# frm-voltrod_AFE.net
KiCad netlist of a schematic drawn in Altium Designer
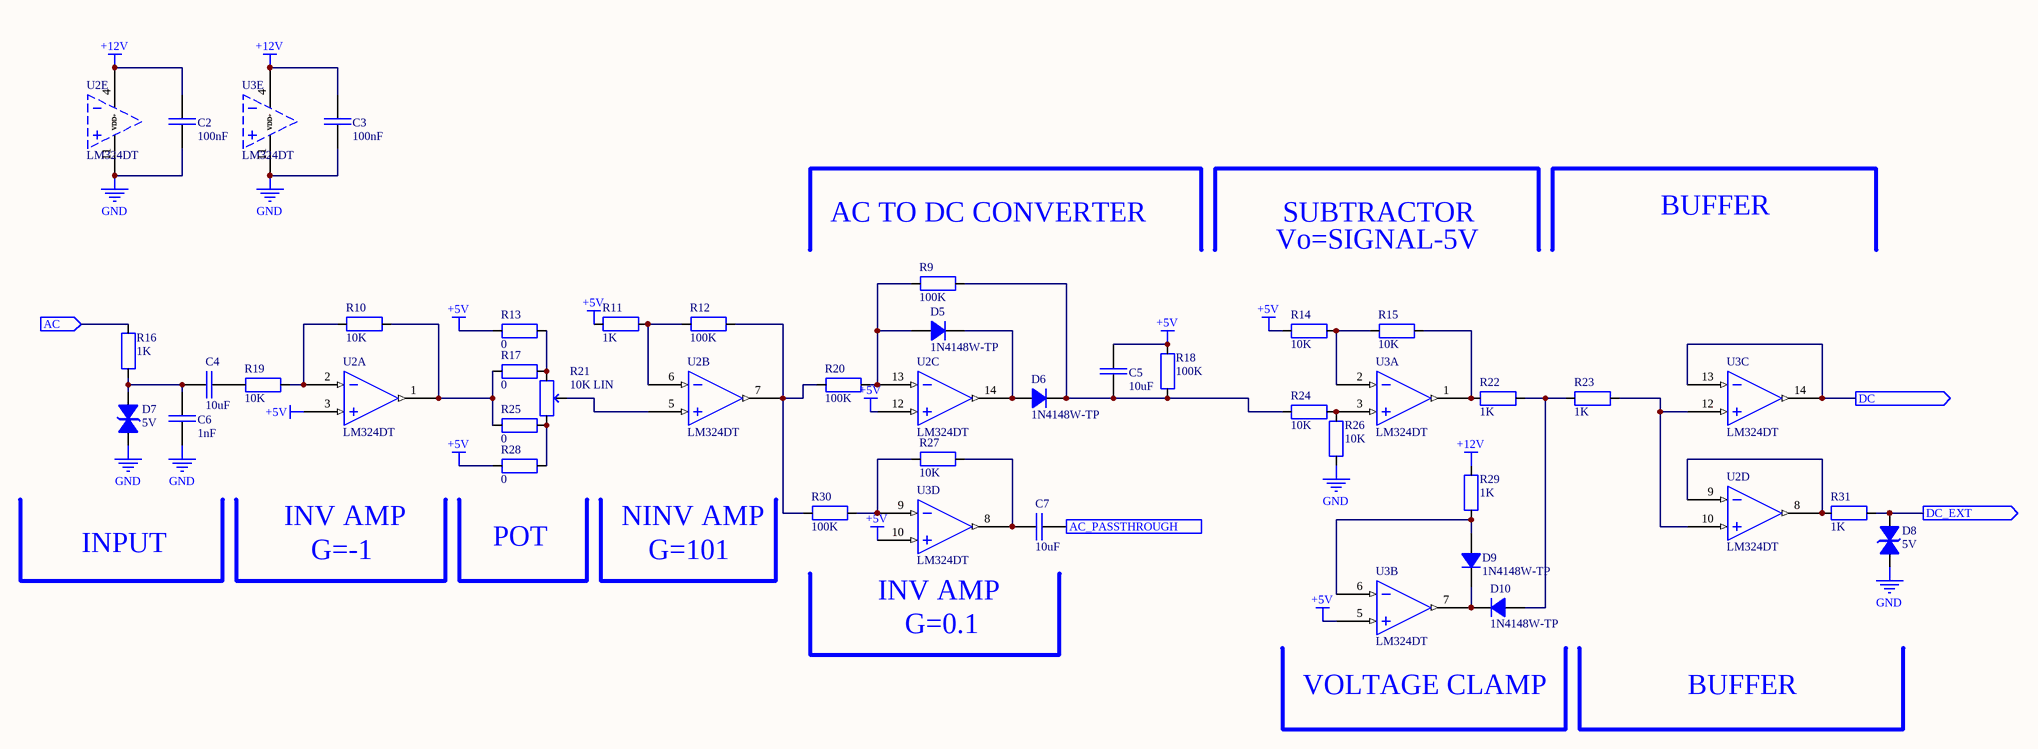
[diagram p0: frm-voltrod_AFE.SchDoc]

(export (version "E")
  (design (tool "Eeschema 10.0.6"))
  (components
    (comp (ref "C2")
      (value "100nF")
      (footprint "CAP 0603_1608")
      (description "CAP SMD MLCC 100nF 25V 0603 X7R")
      (fields (field (name "PART NUMBER") "02841f84-ac15-41b5-9e17-915f8f067828"))
      (libsource (lib "frmdblib") (part "GENERIC_C"))
    )
    (comp (ref "C3")
      (value "100nF")
      (footprint "CAP 0603_1608")
      (description "CAP SMD MLCC 100nF 25V 0603 X7R")
      (fields (field (name "PART NUMBER") "02841f84-ac15-41b5-9e17-915f8f067828"))
      (libsource (lib "frmdblib") (part "GENERIC_C"))
    )
    (comp (ref "C4")
      (value "10uF")
      (footprint "CAP 0805_2012")
      (description "CAP SMD MLCC 10uF 25V 0805 X5R")
      (fields (field (name "PART NUMBER") "1ffbe5a9-0884-4740-bdad-20a6a98400e6"))
      (libsource (lib "frmdblib") (part "GENERIC_C"))
    )
    (comp (ref "C5")
      (value "10uF")
      (footprint "CAP 0805_2012")
      (description "CAP SMD MLCC 10uF 25V 0805 X5R")
      (fields (field (name "PART NUMBER") "1ffbe5a9-0884-4740-bdad-20a6a98400e6"))
      (libsource (lib "frmdblib") (part "GENERIC_C"))
    )
    (comp (ref "C6")
      (value "1nF")
      (footprint "CAP 0603_1608")
      (description "CAP SMD MLCC 1nF 50V 0603 X7R")
      (fields (field (name "PART NUMBER") "0eca2548-3630-4fea-a3d5-94248c1cae74"))
      (libsource (lib "frmdblib") (part "GENERIC_C"))
    )
    (comp (ref "C7")
      (value "10uF")
      (footprint "CAP 0805_2012")
      (description "CAP SMD MLCC 10uF 25V 0805 X5R")
      (fields (field (name "PART NUMBER") "1ffbe5a9-0884-4740-bdad-20a6a98400e6"))
      (libsource (lib "frmdblib") (part "GENERIC_C"))
    )
    (comp (ref "D5")
      (value "1N4148W-TP")
      (footprint "SOD-123")
      (description "DIODE SMD 100V 150mA 1.5Vf SOD-123 4148")
      (fields (field (name "PART NUMBER") "5e920700-75df-48e3-84dd-8f9f777caed8"))
      (libsource (lib "frmdblib") (part "GENERIC_D"))
    )
    (comp (ref "D6")
      (value "1N4148W-TP")
      (footprint "SOD-123")
      (description "DIODE SMD 100V 150mA 1.5Vf SOD-123 4148")
      (fields (field (name "PART NUMBER") "5e920700-75df-48e3-84dd-8f9f777caed8"))
      (libsource (lib "frmdblib") (part "GENERIC_D"))
    )
    (comp (ref "D7")
      (value "5V")
      (footprint "SOD523F")
      (description "DIODE SMD TVS 5V BIDIRECTIONAL SOD-523")
      (fields (field (name "PART NUMBER") "daa58212-38e2-4326-a156-8e48058c46f1"))
      (libsource (lib "frmdblib") (part "GENERIC_D_TVS_BI"))
    )
    (comp (ref "D8")
      (value "5V")
      (footprint "SOD523F")
      (description "DIODE SMD TVS 5V BIDIRECTIONAL SOD-523")
      (fields (field (name "PART NUMBER") "daa58212-38e2-4326-a156-8e48058c46f1"))
      (libsource (lib "frmdblib") (part "GENERIC_D_TVS_BI"))
    )
    (comp (ref "D9")
      (value "1N4148W-TP")
      (footprint "SOD-123")
      (description "DIODE SMD 100V 150mA 1.5Vf SOD-123 4148")
      (fields (field (name "PART NUMBER") "5e920700-75df-48e3-84dd-8f9f777caed8"))
      (libsource (lib "frmdblib") (part "GENERIC_D"))
    )
    (comp (ref "D10")
      (value "1N4148W-TP")
      (footprint "SOD-123")
      (description "DIODE SMD 100V 150mA 1.5Vf SOD-123 4148")
      (fields (field (name "PART NUMBER") "5e920700-75df-48e3-84dd-8f9f777caed8"))
      (libsource (lib "frmdblib") (part "GENERIC_D"))
    )
    (comp (ref "R9")
      (value "100K")
      (footprint "RES 0603_1608")
      (description "RES SMD 100K OHM 1% 1/10W 0603")
      (fields (field (name "PART NUMBER") "76af10b3-9d85-4b5c-a2d6-26cc74f432f7"))
      (libsource (lib "frmdblib") (part "GENERIC_R"))
    )
    (comp (ref "R10")
      (value "10K")
      (footprint "RES 0603_1608")
      (description "RES SMD 10K OHM 1% 1/10W 0603")
      (fields (field (name "PART NUMBER") "93242766-ba1d-462d-b58f-ce1dfc4129c8"))
      (libsource (lib "frmdblib") (part "GENERIC_R"))
    )
    (comp (ref "R11")
      (value "1K")
      (footprint "RES 0603_1608")
      (description "RES SMD 1K OHM 1% 1/10W 0603")
      (fields (field (name "PART NUMBER") "a678220f-9e9d-4863-a833-9993504f723c"))
      (libsource (lib "frmdblib") (part "GENERIC_R"))
    )
    (comp (ref "R12")
      (value "100K")
      (footprint "RES 0603_1608")
      (description "RES SMD 100K OHM 1% 1/10W 0603")
      (fields (field (name "PART NUMBER") "76af10b3-9d85-4b5c-a2d6-26cc74f432f7"))
      (libsource (lib "frmdblib") (part "GENERIC_R"))
    )
    (comp (ref "R13")
      (value "0")
      (footprint "RES 0603_1608")
      (description "RES SMD 0 OHM 5% 1/10W 0603")
      (fields (field (name "PART NUMBER") "6ae227f9-847f-4766-8522-e11a83531204"))
      (libsource (lib "frmdblib") (part "GENERIC_R"))
    )
    (comp (ref "R14")
      (value "10K")
      (footprint "RES 0603_1608")
      (description "RES SMD 10K OHM 1% 1/10W 0603")
      (fields (field (name "PART NUMBER") "93242766-ba1d-462d-b58f-ce1dfc4129c8"))
      (libsource (lib "frmdblib") (part "GENERIC_R"))
    )
    (comp (ref "R15")
      (value "10K")
      (footprint "RES 0603_1608")
      (description "RES SMD 10K OHM 1% 1/10W 0603")
      (fields (field (name "PART NUMBER") "93242766-ba1d-462d-b58f-ce1dfc4129c8"))
      (libsource (lib "frmdblib") (part "GENERIC_R"))
    )
    (comp (ref "R16")
      (value "1K")
      (footprint "RES 0603_1608")
      (description "RES SMD 1K OHM 1% 1/10W 0603")
      (fields (field (name "PART NUMBER") "a678220f-9e9d-4863-a833-9993504f723c"))
      (libsource (lib "frmdblib") (part "GENERIC_R"))
    )
    (comp (ref "R17")
      (value "0")
      (footprint "RES 0603_1608")
      (description "RES SMD 0 OHM 5% 1/10W 0603")
      (fields (field (name "PART NUMBER") "6ae227f9-847f-4766-8522-e11a83531204"))
      (libsource (lib "frmdblib") (part "GENERIC_R"))
    )
    (comp (ref "R18")
      (value "100K")
      (footprint "RES 0603_1608")
      (description "RES SMD 100K OHM 1% 1/10W 0603")
      (fields (field (name "PART NUMBER") "76af10b3-9d85-4b5c-a2d6-26cc74f432f7"))
      (libsource (lib "frmdblib") (part "GENERIC_R"))
    )
    (comp (ref "R19")
      (value "10K")
      (footprint "RES 0603_1608")
      (description "RES SMD 10K OHM 1% 1/10W 0603")
      (fields (field (name "PART NUMBER") "93242766-ba1d-462d-b58f-ce1dfc4129c8"))
      (libsource (lib "frmdblib") (part "GENERIC_R"))
    )
    (comp (ref "R20")
      (value "100K")
      (footprint "RES 0603_1608")
      (description "RES SMD 100K OHM 1% 1/10W 0603")
      (fields (field (name "PART NUMBER") "76af10b3-9d85-4b5c-a2d6-26cc74f432f7"))
      (libsource (lib "frmdblib") (part "GENERIC_R"))
    )
    (comp (ref "R21")
      (value "10K LIN")
      (footprint "2EF88547-EDEF-4A49-A522-C215618D4BC7")
      (description "POT 10K 20% SHAFT 6mmx7.4mm LIN")
      (fields (field (name "PART NUMBER") "3df905ea-1e80-4add-859d-a36edd7f106c"))
      (libsource (lib "frmdblib") (part "GENERIC_R_VAR"))
    )
    (comp (ref "R22")
      (value "1K")
      (footprint "RES 0603_1608")
      (description "RES SMD 1K OHM 1% 1/10W 0603")
      (fields (field (name "PART NUMBER") "a678220f-9e9d-4863-a833-9993504f723c"))
      (libsource (lib "frmdblib") (part "GENERIC_R"))
    )
    (comp (ref "R23")
      (value "1K")
      (footprint "RES 0603_1608")
      (description "RES SMD 1K OHM 1% 1/10W 0603")
      (fields (field (name "PART NUMBER") "a678220f-9e9d-4863-a833-9993504f723c"))
      (libsource (lib "frmdblib") (part "GENERIC_R"))
    )
    (comp (ref "R24")
      (value "10K")
      (footprint "RES 0603_1608")
      (description "RES SMD 10K OHM 1% 1/10W 0603")
      (fields (field (name "PART NUMBER") "93242766-ba1d-462d-b58f-ce1dfc4129c8"))
      (libsource (lib "frmdblib") (part "GENERIC_R"))
    )
    (comp (ref "R25")
      (value "0")
      (footprint "RES 0603_1608")
      (description "RES SMD 0 OHM 5% 1/10W 0603")
      (fields (field (name "PART NUMBER") "6ae227f9-847f-4766-8522-e11a83531204"))
      (libsource (lib "frmdblib") (part "GENERIC_R"))
    )
    (comp (ref "R26")
      (value "10K")
      (footprint "RES 0603_1608")
      (description "RES SMD 10K OHM 1% 1/10W 0603")
      (fields (field (name "PART NUMBER") "93242766-ba1d-462d-b58f-ce1dfc4129c8"))
      (libsource (lib "frmdblib") (part "GENERIC_R"))
    )
    (comp (ref "R27")
      (value "10K")
      (footprint "RES 0603_1608")
      (description "RES SMD 10K OHM 1% 1/10W 0603")
      (fields (field (name "PART NUMBER") "93242766-ba1d-462d-b58f-ce1dfc4129c8"))
      (libsource (lib "frmdblib") (part "GENERIC_R"))
    )
    (comp (ref "R28")
      (value "0")
      (footprint "RES 0603_1608")
      (description "RES SMD 0 OHM 5% 1/10W 0603")
      (fields (field (name "PART NUMBER") "6ae227f9-847f-4766-8522-e11a83531204"))
      (libsource (lib "frmdblib") (part "GENERIC_R"))
    )
    (comp (ref "R29")
      (value "1K")
      (footprint "RES 0603_1608")
      (description "RES SMD 1K OHM 1% 1/10W 0603")
      (fields (field (name "PART NUMBER") "a678220f-9e9d-4863-a833-9993504f723c"))
      (libsource (lib "frmdblib") (part "GENERIC_R"))
    )
    (comp (ref "R30")
      (value "100K")
      (footprint "RES 0603_1608")
      (description "RES SMD 100K OHM 1% 1/10W 0603")
      (fields (field (name "PART NUMBER") "76af10b3-9d85-4b5c-a2d6-26cc74f432f7"))
      (libsource (lib "frmdblib") (part "GENERIC_R"))
    )
    (comp (ref "R31")
      (value "1K")
      (footprint "RES 0603_1608")
      (description "RES SMD 1K OHM 1% 1/10W 0603")
      (fields (field (name "PART NUMBER") "a678220f-9e9d-4863-a833-9993504f723c"))
      (libsource (lib "frmdblib") (part "GENERIC_R"))
    )
    (comp (ref "U2")
      (value "LM324DT")
      (footprint "34355DA5-B1DA-47C2-A88A-ECF82120A4F7")
      (description "IC SMD OPAMP LM324DT SO-14")
      (fields (field (name "PART NUMBER") "21a85167-c328-42f7-a52e-365842c6dad3"))
      (libsource (lib "frmdblib") (part "B8DB4B19-8E9C-4F46-A390-7A352E041443"))
    )
    (comp (ref "U3")
      (value "LM324DT")
      (footprint "34355DA5-B1DA-47C2-A88A-ECF82120A4F7")
      (description "IC SMD OPAMP LM324DT SO-14")
      (fields (field (name "PART NUMBER") "21a85167-c328-42f7-a52e-365842c6dad3"))
      (libsource (lib "frmdblib") (part "B8DB4B19-8E9C-4F46-A390-7A352E041443"))
    )
  )
  (nets
    (net (code "1") (name "+5V") (class "Default")
      (node (ref "C5") (pin "2") (pintype "passive"))
      (node (ref "R11") (pin "2") (pintype "passive"))
      (node (ref "R13") (pin "1") (pintype "passive"))
      (node (ref "R14") (pin "1") (pintype "passive"))
      (node (ref "R18") (pin "1") (pintype "passive"))
      (node (ref "R28") (pin "1") (pintype "passive"))
      (node (ref "U2") (pin "12") (pinfunction "IN+_12") (pintype "input"))
      (node (ref "U2") (pin "3") (pinfunction "IN+_3") (pintype "input"))
      (node (ref "U3") (pin "10") (pinfunction "IN+_10") (pintype "input"))
      (node (ref "U3") (pin "5") (pinfunction "IN+_5") (pintype "input"))
    )
    (net (code "2") (name "+12V") (class "Default")
      (node (ref "C2") (pin "1") (pintype "passive"))
      (node (ref "C3") (pin "1") (pintype "passive"))
      (node (ref "R29") (pin "2") (pintype "passive"))
      (node (ref "U2") (pin "4") (pinfunction "VDD+_4") (pintype "power_in"))
      (node (ref "U3") (pin "4") (pinfunction "VDD+_4") (pintype "power_in"))
    )
    (net (code "3") (name "/AC") (class "Default") (node (ref "R16") (pin "2") (pintype "passive")))
    (net (code "4") (name "/AC_PASSTHROUGH") (class "Default")
      (node (ref "C7") (pin "2") (pintype "passive"))
    )
    (net (code "5") (name "/DC") (class "Default")
      (node (ref "U3") (pin "13") (pinfunction "IN-_13") (pintype "input"))
      (node (ref "U3") (pin "14") (pinfunction "OUT_14") (pintype "output"))
    )
    (net (code "6") (name "/DC_EXT") (class "Default")
      (node (ref "D8") (pin "1") (pintype "passive"))
      (node (ref "R31") (pin "1") (pintype "passive"))
    )
    (net (code "7") (name "GND") (class "Default")
      (node (ref "C2") (pin "2") (pintype "passive"))
      (node (ref "C3") (pin "2") (pintype "passive"))
      (node (ref "C6") (pin "2") (pintype "passive"))
      (node (ref "D7") (pin "2") (pintype "passive"))
      (node (ref "D8") (pin "2") (pintype "passive"))
      (node (ref "R26") (pin "2") (pintype "passive"))
      (node (ref "U2") (pin "11") (pinfunction "VDD-_11") (pintype "power_in"))
      (node (ref "U3") (pin "11") (pinfunction "VDD-_11") (pintype "power_in"))
    )
    (net (code "8") (name "Net-(C4-Pad1)") (class "Default")
      (node (ref "C4") (pin "1") (pintype "passive"))
      (node (ref "C6") (pin "1") (pintype "passive"))
      (node (ref "D7") (pin "1") (pintype "passive"))
      (node (ref "R16") (pin "1") (pintype "passive"))
    )
    (net (code "9") (name "Net-(C4-Pad2)") (class "Default")
      (node (ref "C4") (pin "2") (pintype "passive"))
      (node (ref "R19") (pin "1") (pintype "passive"))
    )
    (net (code "10") (name "Net-(D5-A)") (class "Default")
      (node (ref "D5") (pin "2") (pinfunction "A_2") (pintype "passive"))
      (node (ref "R20") (pin "2") (pintype "passive"))
      (node (ref "R9") (pin "1") (pintype "passive"))
      (node (ref "U2") (pin "13") (pinfunction "IN-_13") (pintype "input"))
    )
    (net (code "11") (name "Net-(D5-K)") (class "Default")
      (node (ref "D5") (pin "1") (pinfunction "K_1") (pintype "passive"))
      (node (ref "D6") (pin "2") (pinfunction "A_2") (pintype "passive"))
      (node (ref "U2") (pin "14") (pinfunction "OUT_14") (pintype "output"))
    )
    (net (code "12") (name "Net-(D6-K)") (class "Default")
      (node (ref "C5") (pin "1") (pintype "passive"))
      (node (ref "D6") (pin "1") (pinfunction "K_1") (pintype "passive"))
      (node (ref "R18") (pin "2") (pintype "passive"))
      (node (ref "R24") (pin "1") (pintype "passive"))
      (node (ref "R9") (pin "2") (pintype "passive"))
    )
    (net (code "13") (name "Net-(D9-A)") (class "Default")
      (node (ref "D9") (pin "2") (pinfunction "A_2") (pintype "passive"))
      (node (ref "R29") (pin "1") (pintype "passive"))
      (node (ref "U3") (pin "6") (pinfunction "IN-_6") (pintype "input"))
    )
    (net (code "14") (name "Net-(D10-A)") (class "Default")
      (node (ref "D10") (pin "2") (pinfunction "A_2") (pintype "passive"))
      (node (ref "R22") (pin "1") (pintype "passive"))
      (node (ref "R23") (pin "2") (pintype "passive"))
    )
    (net (code "15") (name "Net-(D10-K)") (class "Default")
      (node (ref "D10") (pin "1") (pinfunction "K_1") (pintype "passive"))
      (node (ref "D9") (pin "1") (pinfunction "K_1") (pintype "passive"))
      (node (ref "U3") (pin "7") (pinfunction "OUT_7") (pintype "output"))
    )
    (net (code "16") (name "Net-(R13-Pad2)") (class "Default")
      (node (ref "R13") (pin "2") (pintype "passive"))
      (node (ref "R17") (pin "2") (pintype "passive"))
      (node (ref "R21") (pin "1") (pintype "passive"))
    )
    (net (code "17") (name "Net-(R21-Pad3)") (class "Default")
      (node (ref "R21") (pin "3") (pintype "passive"))
      (node (ref "R25") (pin "2") (pintype "passive"))
      (node (ref "R28") (pin "2") (pintype "passive"))
    )
    (net (code "18") (name "Net-(U2A-IN-)") (class "Default")
      (node (ref "R10") (pin "1") (pintype "passive"))
      (node (ref "R19") (pin "2") (pintype "passive"))
      (node (ref "U2") (pin "2") (pinfunction "IN-_2") (pintype "input"))
    )
    (net (code "19") (name "Net-(U2A-OUT)") (class "Default")
      (node (ref "R10") (pin "2") (pintype "passive"))
      (node (ref "R17") (pin "1") (pintype "passive"))
      (node (ref "R25") (pin "1") (pintype "passive"))
      (node (ref "U2") (pin "1") (pinfunction "OUT_1") (pintype "output"))
    )
    (net (code "20") (name "Net-(U2B-IN+)") (class "Default")
      (node (ref "R21") (pin "2") (pintype "passive"))
      (node (ref "U2") (pin "5") (pinfunction "IN+_5") (pintype "input"))
    )
    (net (code "21") (name "Net-(U2B-IN-)") (class "Default")
      (node (ref "R11") (pin "1") (pintype "passive"))
      (node (ref "R12") (pin "1") (pintype "passive"))
      (node (ref "U2") (pin "6") (pinfunction "IN-_6") (pintype "input"))
    )
    (net (code "22") (name "Net-(U2B-OUT)") (class "Default")
      (node (ref "R12") (pin "2") (pintype "passive"))
      (node (ref "R20") (pin "1") (pintype "passive"))
      (node (ref "R30") (pin "1") (pintype "passive"))
      (node (ref "U2") (pin "7") (pinfunction "OUT_7") (pintype "output"))
    )
    (net (code "23") (name "Net-(U2D-IN+)") (class "Default")
      (node (ref "R23") (pin "1") (pintype "passive"))
      (node (ref "U2") (pin "10") (pinfunction "IN+_10") (pintype "input"))
      (node (ref "U3") (pin "12") (pinfunction "IN+_12") (pintype "input"))
    )
    (net (code "24") (name "Net-(U2D-IN-)") (class "Default")
      (node (ref "R31") (pin "2") (pintype "passive"))
      (node (ref "U2") (pin "8") (pinfunction "OUT_8") (pintype "output"))
      (node (ref "U2") (pin "9") (pinfunction "IN-_9") (pintype "input"))
    )
    (net (code "25") (name "Net-(U3A-IN+)") (class "Default")
      (node (ref "R24") (pin "2") (pintype "passive"))
      (node (ref "R26") (pin "1") (pintype "passive"))
      (node (ref "U3") (pin "3") (pinfunction "IN+_3") (pintype "input"))
    )
    (net (code "26") (name "Net-(U3A-IN-)") (class "Default")
      (node (ref "R14") (pin "2") (pintype "passive"))
      (node (ref "R15") (pin "1") (pintype "passive"))
      (node (ref "U3") (pin "2") (pinfunction "IN-_2") (pintype "input"))
    )
    (net (code "27") (name "Net-(U3A-OUT)") (class "Default")
      (node (ref "R15") (pin "2") (pintype "passive"))
      (node (ref "R22") (pin "2") (pintype "passive"))
      (node (ref "U3") (pin "1") (pinfunction "OUT_1") (pintype "output"))
    )
    (net (code "28") (name "Net-(U3D-IN-)") (class "Default")
      (node (ref "R27") (pin "1") (pintype "passive"))
      (node (ref "R30") (pin "2") (pintype "passive"))
      (node (ref "U3") (pin "9") (pinfunction "IN-_9") (pintype "input"))
    )
    (net (code "29") (name "Net-(U3D-OUT)") (class "Default")
      (node (ref "C7") (pin "1") (pintype "passive"))
      (node (ref "R27") (pin "2") (pintype "passive"))
      (node (ref "U3") (pin "8") (pinfunction "OUT_8") (pintype "output"))
    )
  )
)
